# PAGE4_-_SENSORS.net
KiCad netlist of a schematic drawn in Altium Designer
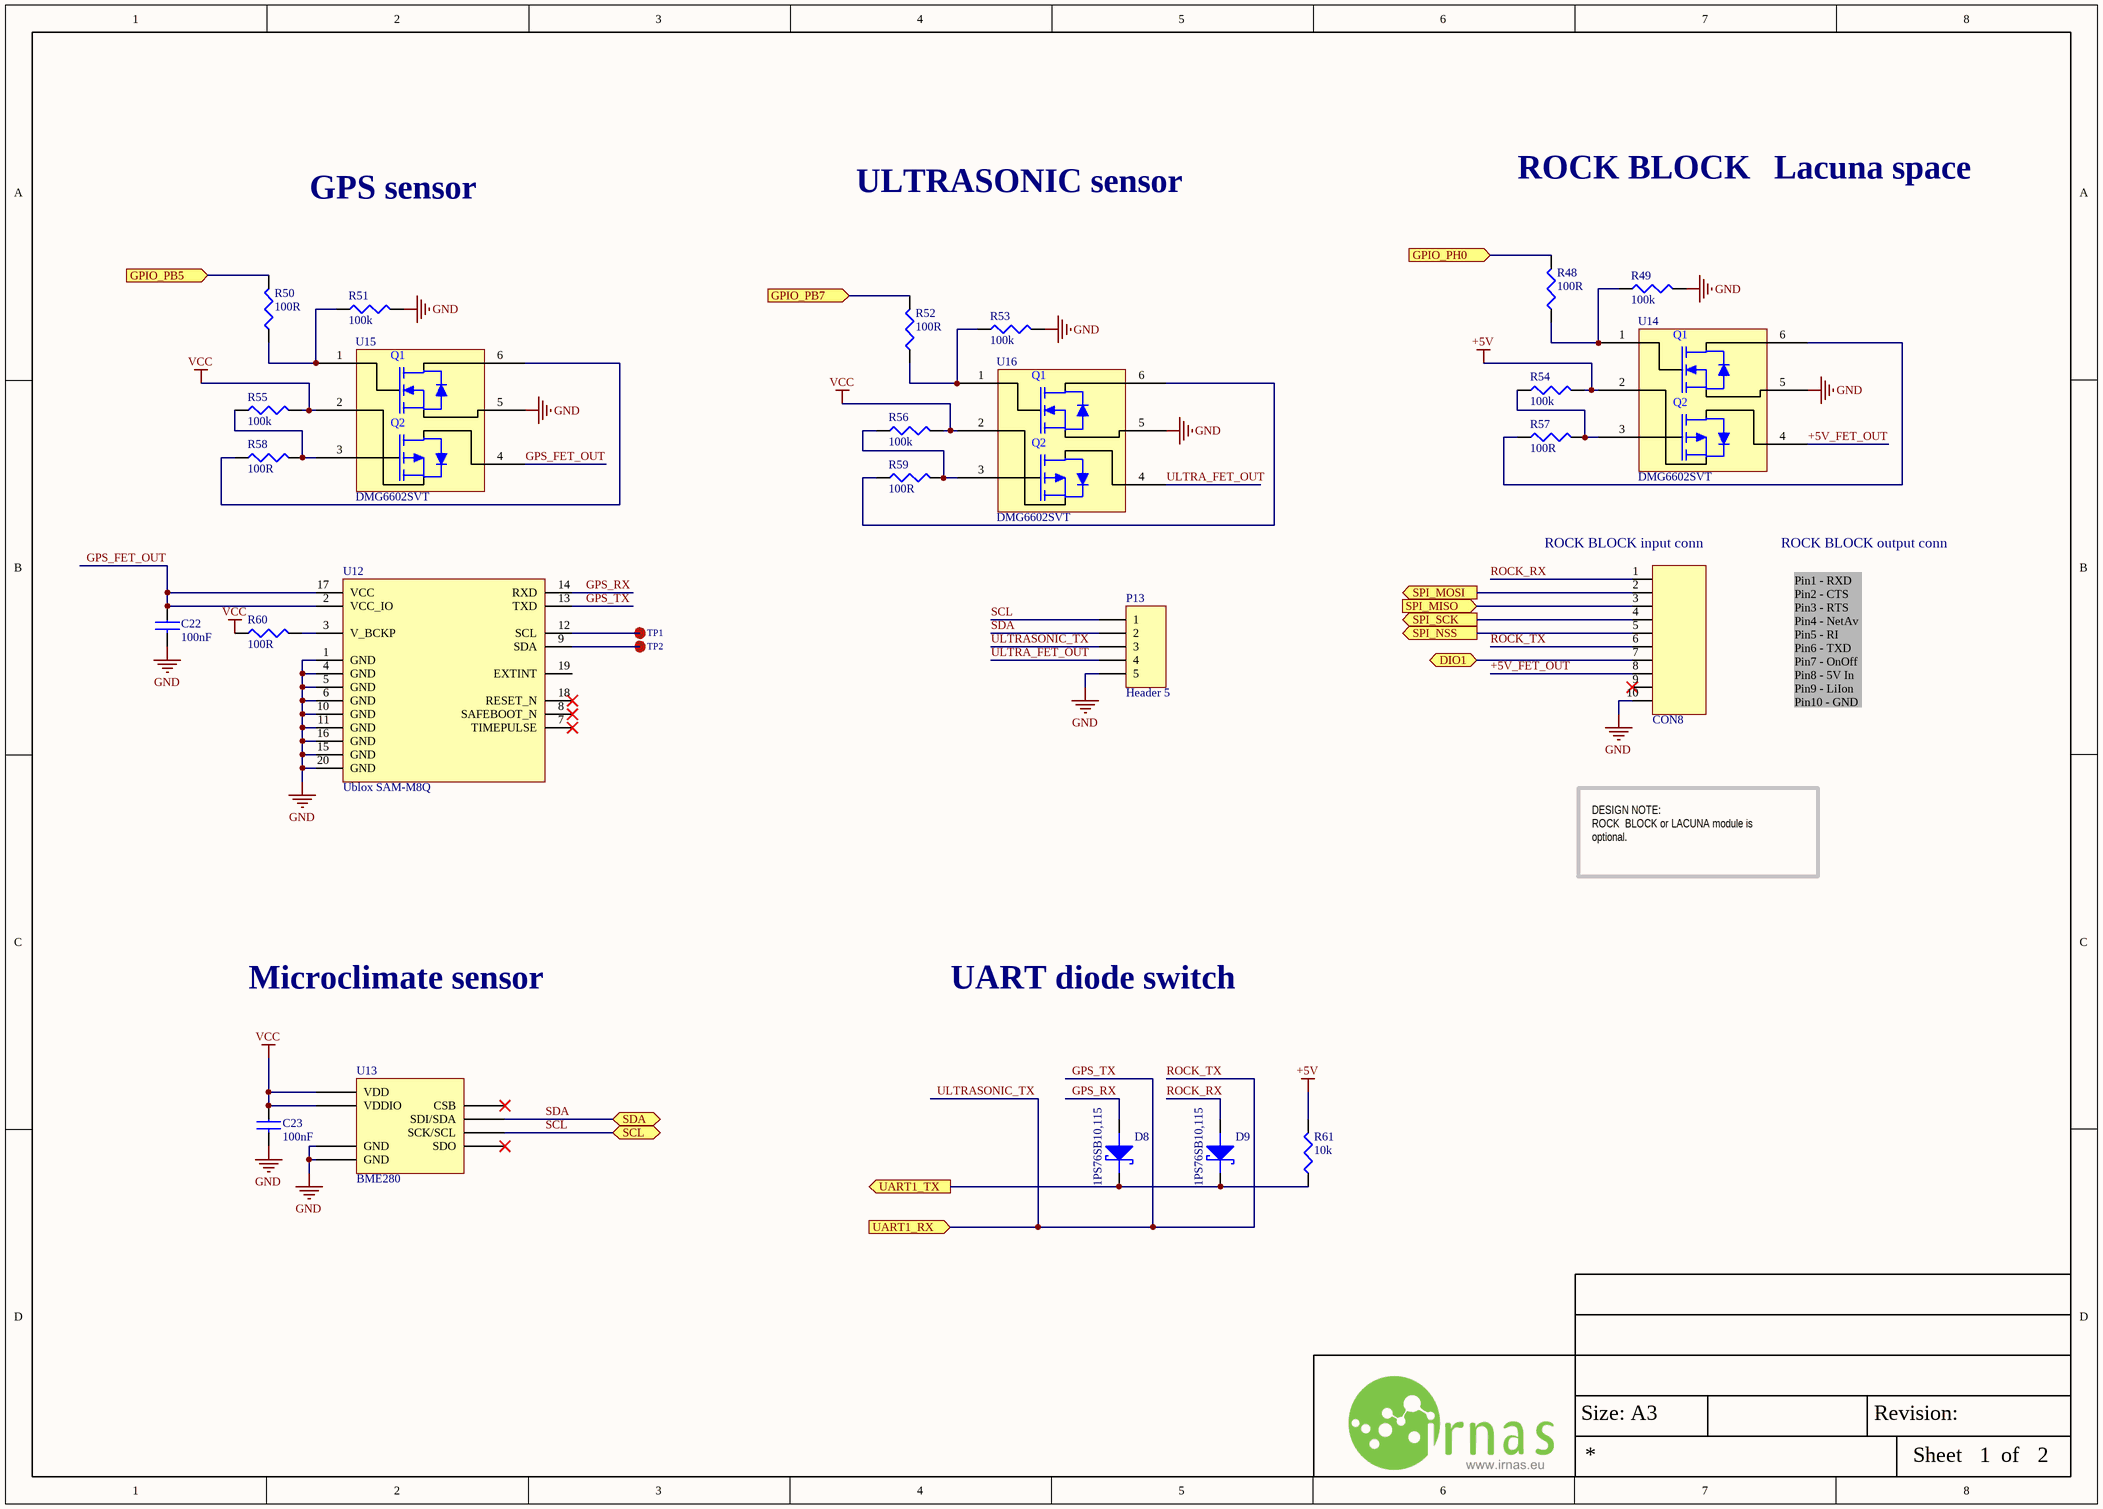
[diagram p0: PAGE4 - SENSORS.SchDoc]

(export (version "E")
  (design (tool "Eeschema 10.0.6"))
  (components
    (comp (ref "C22")
      (value "100nF")
      (footprint "CAP0603")
      (description "MURATA - GRM188R71C104KA01J - CAP, MLCC, X7R, 0.1UF, 16V, 0603")
      (fields
        (field (name "MANUFACTURER") "MURATA")
        (field (name "MANUFACTURER PART NUMBER") "GRM188R71C104KA01J")
      )
      (libsource (lib "Passive") (part "C - 100nF"))
    )
    (comp (ref "C23")
      (value "100nF")
      (footprint "CAP0603")
      (description "MURATA - GRM188R71C104KA01J - CAP, MLCC, X7R, 0.1UF, 16V, 0603")
      (fields
        (field (name "MANUFACTURER") "MURATA")
        (field (name "MANUFACTURER PART NUMBER") "GRM188R71C104KA01J")
      )
      (libsource (lib "Passive") (part "C - 100nF"))
    )
    (comp (ref "CON8")
      (value "53261-1071")
      (footprint "PICOBLADE 10PIN")
      (description "Wire-To-Board Connector, Right Angle, 1.25 mm, 10 Contacts, Header, PicoBlade 53261 Series")
      (libsource (lib "Connectors") (part "PicoBlade 10pin"))
    )
    (comp (ref "D8")
      (value "1PS76SB10,115")
      (footprint "SOD-323")
      (description "Small Signal Schottky Diode, Single, 30 V, 200 mA, 320 mV, 800 mA, 125 °C")
      (libsource (lib "Active") (part "DS - 1PS76SB10,115"))
    )
    (comp (ref "D9")
      (value "1PS76SB10,115")
      (footprint "SOD-323")
      (description "Small Signal Schottky Diode, Single, 30 V, 200 mA, 320 mV, 800 mA, 125 °C")
      (libsource (lib "Active") (part "DS - 1PS76SB10,115"))
    )
    (comp (ref "P13")
      (value "Header 5")
      (footprint "HDR1X5")
      (description "Header, 5-Pin")
      (fields (field (name "PUBLISHER") "Altium Limited"))
      (libsource (lib "Miscellaneous Connectors") (part "Header 5"))
    )
    (comp (ref "R48")
      (value "100R")
      (footprint "RES0603")
      (description "MULTICOMP - MC0063W06031100R - RES, THICK FILM, 100R, 1%, 0.063W, 0603")
      (fields
        (field (name "MANUFACTURER") "MULTICOMP")
        (field (name "MANUFACTURER PART NUMBER") "MC0063W06031100R")
      )
      (libsource (lib "Passive") (part "R - 100R"))
    )
    (comp (ref "R49")
      (value "100k")
      (footprint "RES0603")
      (description "MULTICOMP - MCMR06X104 JTL - RES, CERAMIC, 100K, 5%, 0.1W, 0603")
      (fields
        (field (name "MANUFACTURER") "MULTICOMP")
        (field (name "MANUFACTURER PART NUMBER") "MCMR06X104 JTL")
      )
      (libsource (lib "Passive") (part "R - 100k"))
    )
    (comp (ref "R50")
      (value "100R")
      (footprint "RES0603")
      (description "MULTICOMP - MC0063W06031100R - RES, THICK FILM, 100R, 1%, 0.063W, 0603")
      (fields
        (field (name "MANUFACTURER") "MULTICOMP")
        (field (name "MANUFACTURER PART NUMBER") "MC0063W06031100R")
      )
      (libsource (lib "Passive") (part "R - 100R"))
    )
    (comp (ref "R51")
      (value "100k")
      (footprint "RES0603")
      (description "MULTICOMP - MCMR06X104 JTL - RES, CERAMIC, 100K, 5%, 0.1W, 0603")
      (fields
        (field (name "MANUFACTURER") "MULTICOMP")
        (field (name "MANUFACTURER PART NUMBER") "MCMR06X104 JTL")
      )
      (libsource (lib "Passive") (part "R - 100k"))
    )
    (comp (ref "R52")
      (value "100R")
      (footprint "RES0603")
      (description "MULTICOMP - MC0063W06031100R - RES, THICK FILM, 100R, 1%, 0.063W, 0603")
      (fields
        (field (name "MANUFACTURER") "MULTICOMP")
        (field (name "MANUFACTURER PART NUMBER") "MC0063W06031100R")
      )
      (libsource (lib "Passive") (part "R - 100R"))
    )
    (comp (ref "R53")
      (value "100k")
      (footprint "RES0603")
      (description "MULTICOMP - MCMR06X104 JTL - RES, CERAMIC, 100K, 5%, 0.1W, 0603")
      (fields
        (field (name "MANUFACTURER") "MULTICOMP")
        (field (name "MANUFACTURER PART NUMBER") "MCMR06X104 JTL")
      )
      (libsource (lib "Passive") (part "R - 100k"))
    )
    (comp (ref "R54")
      (value "100k")
      (footprint "RES0603")
      (description "MULTICOMP - MCMR06X104 JTL - RES, CERAMIC, 100K, 5%, 0.1W, 0603")
      (fields
        (field (name "MANUFACTURER") "MULTICOMP")
        (field (name "MANUFACTURER PART NUMBER") "MCMR06X104 JTL")
      )
      (libsource (lib "Passive") (part "R - 100k"))
    )
    (comp (ref "R55")
      (value "100k")
      (footprint "RES0603")
      (description "MULTICOMP - MCMR06X104 JTL - RES, CERAMIC, 100K, 5%, 0.1W, 0603")
      (fields
        (field (name "MANUFACTURER") "MULTICOMP")
        (field (name "MANUFACTURER PART NUMBER") "MCMR06X104 JTL")
      )
      (libsource (lib "Passive") (part "R - 100k"))
    )
    (comp (ref "R56")
      (value "100k")
      (footprint "RES0603")
      (description "MULTICOMP - MCMR06X104 JTL - RES, CERAMIC, 100K, 5%, 0.1W, 0603")
      (fields
        (field (name "MANUFACTURER") "MULTICOMP")
        (field (name "MANUFACTURER PART NUMBER") "MCMR06X104 JTL")
      )
      (libsource (lib "Passive") (part "R - 100k"))
    )
    (comp (ref "R57")
      (value "100R")
      (footprint "RES0603")
      (description "MULTICOMP - MC0063W06031100R - RES, THICK FILM, 100R, 1%, 0.063W, 0603")
      (fields
        (field (name "MANUFACTURER") "MULTICOMP")
        (field (name "MANUFACTURER PART NUMBER") "MC0063W06031100R")
      )
      (libsource (lib "Passive") (part "R - 100R"))
    )
    (comp (ref "R58")
      (value "100R")
      (footprint "RES0603")
      (description "MULTICOMP - MC0063W06031100R - RES, THICK FILM, 100R, 1%, 0.063W, 0603")
      (fields
        (field (name "MANUFACTURER") "MULTICOMP")
        (field (name "MANUFACTURER PART NUMBER") "MC0063W06031100R")
      )
      (libsource (lib "Passive") (part "R - 100R"))
    )
    (comp (ref "R59")
      (value "100R")
      (footprint "RES0603")
      (description "MULTICOMP - MC0063W06031100R - RES, THICK FILM, 100R, 1%, 0.063W, 0603")
      (fields
        (field (name "MANUFACTURER") "MULTICOMP")
        (field (name "MANUFACTURER PART NUMBER") "MC0063W06031100R")
      )
      (libsource (lib "Passive") (part "R - 100R"))
    )
    (comp (ref "R60")
      (value "100R")
      (footprint "RES0603")
      (description "MULTICOMP - MC0063W06031100R - RES, THICK FILM, 100R, 1%, 0.063W, 0603")
      (fields
        (field (name "MANUFACTURER") "MULTICOMP")
        (field (name "MANUFACTURER PART NUMBER") "MC0063W06031100R")
      )
      (libsource (lib "Passive") (part "R - 100R"))
    )
    (comp (ref "R61")
      (value "10k")
      (footprint "RES0603")
      (description "MULTICOMP - MCMR06X103 JTL - RES, CERAMIC, 10K, 5%, 0.1W, 0603")
      (fields
        (field (name "MANUFACTURER") "MULTICOMP")
        (field (name "MANUFACTURER PART NUMBER") "MCMR06X103 JTL")
      )
      (libsource (lib "Passive") (part "R - 10k"))
    )
    (comp (ref "TP1")
      (value "TestPoint")
      (footprint "Passive:TestPoint:1.2x1.2mm")
      (description "TEST POINT ROUND SMD")
      (libsource (lib "Passive") (part "TestPoint"))
    )
    (comp (ref "TP2")
      (value "TestPoint")
      (footprint "Passive:TestPoint:1.2x1.2mm")
      (description "TEST POINT ROUND SMD")
      (libsource (lib "Passive") (part "TestPoint"))
    )
    (comp (ref "U12")
      (value "Ublox SAM-M8Q")
      (footprint "SAM-M8Q")
      (description "SAM-M8 RF Receiver BeiDou, Galileo, GLONASS, GNSS, GPS -160dBm")
      (fields (field (name "MANUFACTURER") "u-blox") (field (name "MANUFACTURER PART NUMBER") "MAX-M8Q-0"))
      (libsource (lib "Active") (part "RF - UBLOX-SAM-M8Q"))
    )
    (comp (ref "U13")
      (value "BME280")
      (footprint "BME280")
      (description "Humidity Temperature Sensor 0 ~ 100% RH I²C, SPI ±3% 1s Surface Mount")
      (libsource (lib "Active") (part "SEN - BME280"))
    )
    (comp (ref "U14")
      (value "DMG6602SVT")
      (footprint "TSOT26")
      (description "Dual MOSFET, N and P Channel, 3.4 A, 30 V, 0.038 ohm, 10 V, 1 V")
      (libsource (lib "Active") (part "T_M - DMG6602SVT"))
    )
    (comp (ref "U15")
      (value "DMG6602SVT")
      (footprint "TSOT26")
      (description "Dual MOSFET, N and P Channel, 3.4 A, 30 V, 0.038 ohm, 10 V, 1 V")
      (libsource (lib "Active") (part "T_M - DMG6602SVT"))
    )
    (comp (ref "U16")
      (value "DMG6602SVT")
      (footprint "TSOT26")
      (description "Dual MOSFET, N and P Channel, 3.4 A, 30 V, 0.038 ohm, 10 V, 1 V")
      (libsource (lib "Active") (part "T_M - DMG6602SVT"))
    )
  )
  (nets
    (net (code "1") (name "+5V") (class "Default")
      (node (ref "R54") (pin "2") (pinfunction "2_2") (pintype "passive"))
      (node (ref "R61") (pin "2") (pinfunction "2_2") (pintype "passive"))
      (node (ref "U14") (pin "2") (pinfunction "S2_2") (pintype "open_collector"))
    )
    (net (code "2") (name "/+5V_FET_OUT") (class "Default")
      (node (ref "CON8") (pin "8") (pinfunction "8_8") (pintype "passive"))
      (node (ref "U14") (pin "4") (pinfunction "D2_4") (pintype "open_collector"))
    )
    (net (code "3") (name "/DIO1") (class "Default")
      (node (ref "CON8") (pin "7") (pinfunction "7_7") (pintype "passive"))
    )
    (net (code "4") (name "/GPIO_PB5") (class "Default")
      (node (ref "R50") (pin "2") (pinfunction "2_2") (pintype "passive"))
    )
    (net (code "5") (name "/GPIO_PB7") (class "Default")
      (node (ref "R52") (pin "2") (pinfunction "2_2") (pintype "passive"))
    )
    (net (code "6") (name "/GPIO_PH0") (class "Default")
      (node (ref "R48") (pin "2") (pinfunction "2_2") (pintype "passive"))
    )
    (net (code "7") (name "/GPS_FET_OUT") (class "Default")
      (node (ref "C22") (pin "1") (pinfunction "1_1") (pintype "passive"))
      (node (ref "U12") (pin "17") (pinfunction "VCC_17") (pintype "passive"))
      (node (ref "U12") (pin "2") (pinfunction "VCC_IO_2") (pintype "passive"))
      (node (ref "U15") (pin "4") (pinfunction "D2_4") (pintype "open_collector"))
    )
    (net (code "8") (name "/GPS_RX") (class "Default")
      (node (ref "D8") (pin "2") (pinfunction "ANODE_2") (pintype "passive"))
      (node (ref "U12") (pin "14") (pinfunction "RXD_14") (pintype "passive"))
    )
    (net (code "9") (name "/GPS_TX") (class "Default")
      (node (ref "CON8") (pin "6") (pinfunction "6_6") (pintype "passive"))
      (node (ref "P13") (pin "3") (pinfunction "3_3") (pintype "passive"))
      (node (ref "U12") (pin "13") (pinfunction "TXD_13") (pintype "passive"))
    )
    (net (code "10") (name "/ROCK_RX") (class "Default")
      (node (ref "CON8") (pin "1") (pinfunction "1_1") (pintype "passive"))
      (node (ref "D9") (pin "2") (pinfunction "ANODE_2") (pintype "passive"))
    )
    (net (code "11") (name "/SCL") (class "Default")
      (node (ref "P13") (pin "1") (pinfunction "1_1") (pintype "passive"))
      (node (ref "U13") (pin "4") (pinfunction "SCK/SCL_4") (pintype "passive"))
    )
    (net (code "12") (name "/SDA") (class "Default")
      (node (ref "P13") (pin "2") (pinfunction "2_2") (pintype "passive"))
      (node (ref "U13") (pin "3") (pinfunction "SDI/SDA_3") (pintype "passive"))
    )
    (net (code "13") (name "/SPI_MISO") (class "Default")
      (node (ref "CON8") (pin "3") (pinfunction "3_3") (pintype "passive"))
    )
    (net (code "14") (name "/SPI_MOSI") (class "Default")
      (node (ref "CON8") (pin "2") (pinfunction "2_2") (pintype "passive"))
    )
    (net (code "15") (name "/SPI_NSS") (class "Default")
      (node (ref "CON8") (pin "5") (pinfunction "5_5") (pintype "passive"))
    )
    (net (code "16") (name "/SPI_SCK") (class "Default")
      (node (ref "CON8") (pin "4") (pinfunction "4_4") (pintype "passive"))
    )
    (net (code "17") (name "/UART1_TX") (class "Default")
      (node (ref "D8") (pin "1") (pinfunction "cathode_1") (pintype "passive"))
      (node (ref "D9") (pin "1") (pinfunction "cathode_1") (pintype "passive"))
      (node (ref "R61") (pin "1") (pinfunction "1_1") (pintype "passive"))
    )
    (net (code "18") (name "/ULTRA_FET_OUT") (class "Default")
      (node (ref "P13") (pin "4") (pinfunction "4_4") (pintype "passive"))
      (node (ref "U16") (pin "4") (pinfunction "D2_4") (pintype "open_collector"))
    )
    (net (code "19") (name "GND") (class "Default")
      (node (ref "C22") (pin "2") (pinfunction "2_2") (pintype "passive"))
      (node (ref "C23") (pin "2") (pinfunction "2_2") (pintype "passive"))
      (node (ref "CON8") (pin "10") (pinfunction "10_10") (pintype "passive"))
      (node (ref "P13") (pin "5") (pinfunction "5_5") (pintype "passive"))
      (node (ref "R49") (pin "2") (pinfunction "2_2") (pintype "passive"))
      (node (ref "R51") (pin "2") (pinfunction "2_2") (pintype "passive"))
      (node (ref "R53") (pin "2") (pinfunction "2_2") (pintype "passive"))
      (node (ref "U12") (pin "1") (pinfunction "GND_1") (pintype "passive"))
      (node (ref "U12") (pin "10") (pinfunction "GND_10") (pintype "passive"))
      (node (ref "U12") (pin "11") (pinfunction "GND_11") (pintype "passive"))
      (node (ref "U12") (pin "15") (pinfunction "GND_15") (pintype "passive"))
      (node (ref "U12") (pin "16") (pinfunction "GND_16") (pintype "passive"))
      (node (ref "U12") (pin "20") (pinfunction "GND_20") (pintype "passive"))
      (node (ref "U12") (pin "4") (pinfunction "GND_4") (pintype "passive"))
      (node (ref "U12") (pin "5") (pinfunction "GND_5") (pintype "passive"))
      (node (ref "U12") (pin "6") (pinfunction "GND_6") (pintype "passive"))
      (node (ref "U13") (pin "1") (pinfunction "GND_1") (pintype "passive"))
      (node (ref "U13") (pin "7") (pinfunction "GND_7") (pintype "passive"))
      (node (ref "U14") (pin "5") (pinfunction "S1_5") (pintype "open_collector"))
      (node (ref "U15") (pin "5") (pinfunction "S1_5") (pintype "open_collector"))
      (node (ref "U16") (pin "5") (pinfunction "S1_5") (pintype "open_collector"))
    )
    (net (code "20") (name "Net-(U12-SCL)") (class "Default")
      (node (ref "TP1") (pin "0") (pinfunction "0_0") (pintype "passive"))
      (node (ref "U12") (pin "12") (pinfunction "SCL_12") (pintype "passive"))
    )
    (net (code "21") (name "Net-(U12-SDA)") (class "Default")
      (node (ref "TP2") (pin "0") (pinfunction "0_0") (pintype "passive"))
      (node (ref "U12") (pin "9") (pinfunction "SDA_9") (pintype "passive"))
    )
    (net (code "22") (name "Net-(U12-V_BCKP)") (class "Default")
      (node (ref "R60") (pin "2") (pinfunction "2_2") (pintype "passive"))
      (node (ref "U12") (pin "3") (pinfunction "V_BCKP_3") (pintype "passive"))
    )
    (net (code "23") (name "Net-(U14-D1)") (class "Default")
      (node (ref "R57") (pin "1") (pinfunction "1_1") (pintype "passive"))
      (node (ref "U14") (pin "6") (pinfunction "D1_6") (pintype "open_collector"))
    )
    (net (code "24") (name "Net-(U14-G1)") (class "Default")
      (node (ref "R48") (pin "1") (pinfunction "1_1") (pintype "passive"))
      (node (ref "R49") (pin "1") (pinfunction "1_1") (pintype "passive"))
      (node (ref "U14") (pin "1") (pinfunction "G1_1") (pintype "open_collector"))
    )
    (net (code "25") (name "Net-(U14-G2)") (class "Default")
      (node (ref "R54") (pin "1") (pinfunction "1_1") (pintype "passive"))
      (node (ref "R57") (pin "2") (pinfunction "2_2") (pintype "passive"))
      (node (ref "U14") (pin "3") (pinfunction "G2_3") (pintype "open_collector"))
    )
    (net (code "26") (name "Net-(U15-D1)") (class "Default")
      (node (ref "R58") (pin "1") (pinfunction "1_1") (pintype "passive"))
      (node (ref "U15") (pin "6") (pinfunction "D1_6") (pintype "open_collector"))
    )
    (net (code "27") (name "Net-(U15-G1)") (class "Default")
      (node (ref "R50") (pin "1") (pinfunction "1_1") (pintype "passive"))
      (node (ref "R51") (pin "1") (pinfunction "1_1") (pintype "passive"))
      (node (ref "U15") (pin "1") (pinfunction "G1_1") (pintype "open_collector"))
    )
    (net (code "28") (name "Net-(U15-G2)") (class "Default")
      (node (ref "R55") (pin "1") (pinfunction "1_1") (pintype "passive"))
      (node (ref "R58") (pin "2") (pinfunction "2_2") (pintype "passive"))
      (node (ref "U15") (pin "3") (pinfunction "G2_3") (pintype "open_collector"))
    )
    (net (code "29") (name "Net-(U16-D1)") (class "Default")
      (node (ref "R59") (pin "1") (pinfunction "1_1") (pintype "passive"))
      (node (ref "U16") (pin "6") (pinfunction "D1_6") (pintype "open_collector"))
    )
    (net (code "30") (name "Net-(U16-G1)") (class "Default")
      (node (ref "R52") (pin "1") (pinfunction "1_1") (pintype "passive"))
      (node (ref "R53") (pin "1") (pinfunction "1_1") (pintype "passive"))
      (node (ref "U16") (pin "1") (pinfunction "G1_1") (pintype "open_collector"))
    )
    (net (code "31") (name "Net-(U16-G2)") (class "Default")
      (node (ref "R56") (pin "1") (pinfunction "1_1") (pintype "passive"))
      (node (ref "R59") (pin "2") (pinfunction "2_2") (pintype "passive"))
      (node (ref "U16") (pin "3") (pinfunction "G2_3") (pintype "open_collector"))
    )
    (net (code "32") (name "VCC") (class "Default")
      (node (ref "C23") (pin "1") (pinfunction "1_1") (pintype "passive"))
      (node (ref "R55") (pin "2") (pinfunction "2_2") (pintype "passive"))
      (node (ref "R56") (pin "2") (pinfunction "2_2") (pintype "passive"))
      (node (ref "R60") (pin "1") (pinfunction "1_1") (pintype "passive"))
      (node (ref "U13") (pin "6") (pinfunction "VDDIO_6") (pintype "passive"))
      (node (ref "U13") (pin "8") (pinfunction "VDD_8") (pintype "passive"))
      (node (ref "U15") (pin "2") (pinfunction "S2_2") (pintype "open_collector"))
      (node (ref "U16") (pin "2") (pinfunction "S2_2") (pintype "open_collector"))
    )
    (net (code "33") (name "unconnected-(CON8-Pad9)") (class "Default")
      (node (ref "CON8") (pin "9") (pinfunction "9_9") (pintype "passive+no_connect"))
    )
    (net (code "34") (name "unconnected-(U12-EXTINT-Pad19)") (class "Default")
      (node (ref "U12") (pin "19") (pinfunction "EXTINT_19") (pintype "passive"))
    )
    (net (code "35") (name "unconnected-(U12-RESET_N-Pad18)") (class "Default")
      (node (ref "U12") (pin "18") (pinfunction "RESET_N_18") (pintype "passive+no_connect"))
    )
    (net (code "36") (name "unconnected-(U12-SAFEBOOT_N-Pad8)") (class "Default")
      (node (ref "U12") (pin "8") (pinfunction "SAFEBOOT_N_8") (pintype "passive+no_connect"))
    )
    (net (code "37") (name "unconnected-(U12-TIMEPULSE-Pad7)") (class "Default")
      (node (ref "U12") (pin "7") (pinfunction "TIMEPULSE_7") (pintype "passive+no_connect"))
    )
    (net (code "38") (name "unconnected-(U13-CSB-Pad2)") (class "Default")
      (node (ref "U13") (pin "2") (pinfunction "CSB_2") (pintype "passive+no_connect"))
    )
    (net (code "39") (name "unconnected-(U13-SDO-Pad5)") (class "Default")
      (node (ref "U13") (pin "5") (pinfunction "SDO_5") (pintype "passive+no_connect"))
    )
  )
)
